# LDO_Converter_Schematic.net
KiCad netlist of a schematic drawn in Altium Designer
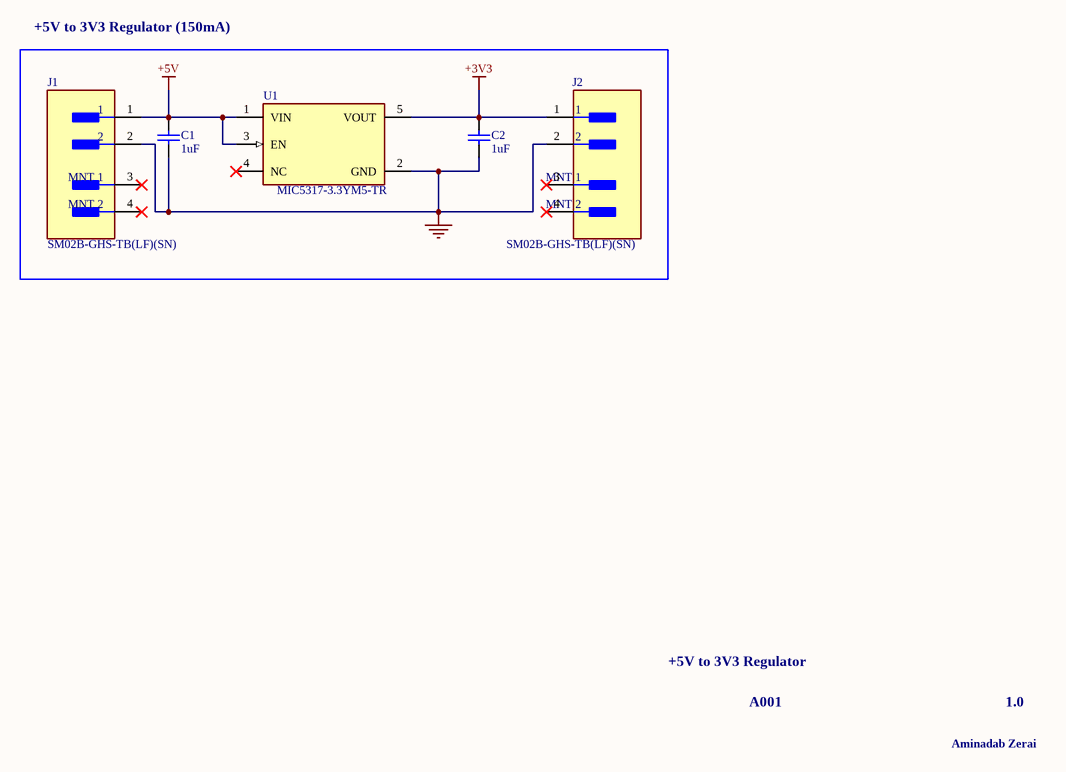
[diagram p0: LDO_Converter_Schematic.SchDoc]

(export (version "E")
  (design (tool "Eeschema 10.0.6"))
  (components
    (comp (ref "C1")
      (value "1uF")
      (footprint "CAPC2013X145X50NL20T20")
      (fields (field (name "PART NUMBER") "VJ0805Y105KXQRW1BC") (field (name "MANUFACTURER") "Vitramon"))
      (libsource (lib "Altium Content Vault") (part "CAP"))
    )
    (comp (ref "C2")
      (value "1uF")
      (footprint "CAPC2013X145X50NL20T20")
      (fields (field (name "PART NUMBER") "VJ0805Y105KXQRW1BC") (field (name "MANUFACTURER") "Vitramon"))
      (libsource (lib "Altium Content Vault") (part "CAP"))
    )
    (comp (ref "J1")
      (value "SM02B-GHS-TB(LF)(SN)")
      (footprint "FP-SM02B-GHS-TB_LF_SN-MFG")
      (description "CONN HEADER SMD R/A 2POS 1.25MM")
      (libsource (lib "") (part "56ec3178a87b3978bdc1b3682cd516a_1"))
    )
    (comp (ref "J2")
      (value "SM02B-GHS-TB(LF)(SN)")
      (footprint "FP-SM02B-GHS-TB_LF_SN-MFG")
      (description "CONN HEADER SMD R/A 2POS 1.25MM")
      (libsource (lib "Altium Content Vault") (part "56ec3178a87b3978bdc1b3682cd516a"))
    )
    (comp (ref "U1")
      (value "MIC5317-3.3YM5-TR")
      (footprint "FP-SOT23-5LD-PL-1-MFG")
      (description "IC REG LINEAR 3.3V 150MA SOT23-5")
      (libsource (lib "Altium Content Vault") (part "0a093dae7315cdc977fd108dde87457"))
    )
  )
  (nets
    (net (code "1") (name "+3V3") (class "Default")
      (node (ref "C2") (pin "2") (pinfunction "2_2") (pintype "passive"))
      (node (ref "J2") (pin "1") (pinfunction "1_1") (pintype "passive"))
      (node (ref "U1") (pin "5") (pinfunction "VOUT_5") (pintype "power_in"))
    )
    (net (code "2") (name "+5V") (class "Default")
      (node (ref "C1") (pin "1") (pinfunction "1_1") (pintype "passive"))
      (node (ref "J1") (pin "1") (pinfunction "1_1") (pintype "passive"))
      (node (ref "U1") (pin "1") (pinfunction "VIN_1") (pintype "power_in"))
      (node (ref "U1") (pin "3") (pinfunction "EN_3") (pintype "input"))
    )
    (net (code "3") (name "GND") (class "Default")
      (node (ref "C1") (pin "2") (pinfunction "2_2") (pintype "passive"))
      (node (ref "C2") (pin "1") (pinfunction "1_1") (pintype "passive"))
      (node (ref "J1") (pin "2") (pinfunction "2_2") (pintype "passive"))
      (node (ref "J2") (pin "2") (pinfunction "2_2") (pintype "passive"))
      (node (ref "U1") (pin "2") (pinfunction "GND_2") (pintype "power_in"))
    )
    (net (code "4") (name "unconnected-(J1-MNT_1-Pad3)") (class "Default")
      (node (ref "J1") (pin "3") (pinfunction "MNT_1_3") (pintype "passive+no_connect"))
    )
    (net (code "5") (name "unconnected-(J1-MNT_2-Pad4)") (class "Default")
      (node (ref "J1") (pin "4") (pinfunction "MNT_2_4") (pintype "passive+no_connect"))
    )
    (net (code "6") (name "unconnected-(J2-MNT_1-Pad3)") (class "Default")
      (node (ref "J2") (pin "3") (pinfunction "MNT_1_3") (pintype "passive+no_connect"))
    )
    (net (code "7") (name "unconnected-(J2-MNT_2-Pad4)") (class "Default")
      (node (ref "J2") (pin "4") (pinfunction "MNT_2_4") (pintype "passive+no_connect"))
    )
    (net (code "8") (name "unconnected-(U1-NC-Pad4)") (class "Default")
      (node (ref "U1") (pin "4") (pinfunction "NC_4") (pintype "passive+no_connect"))
    )
  )
)
